# Ethernet_Switch.net
KiCad netlist of a schematic drawn in Altium Designer
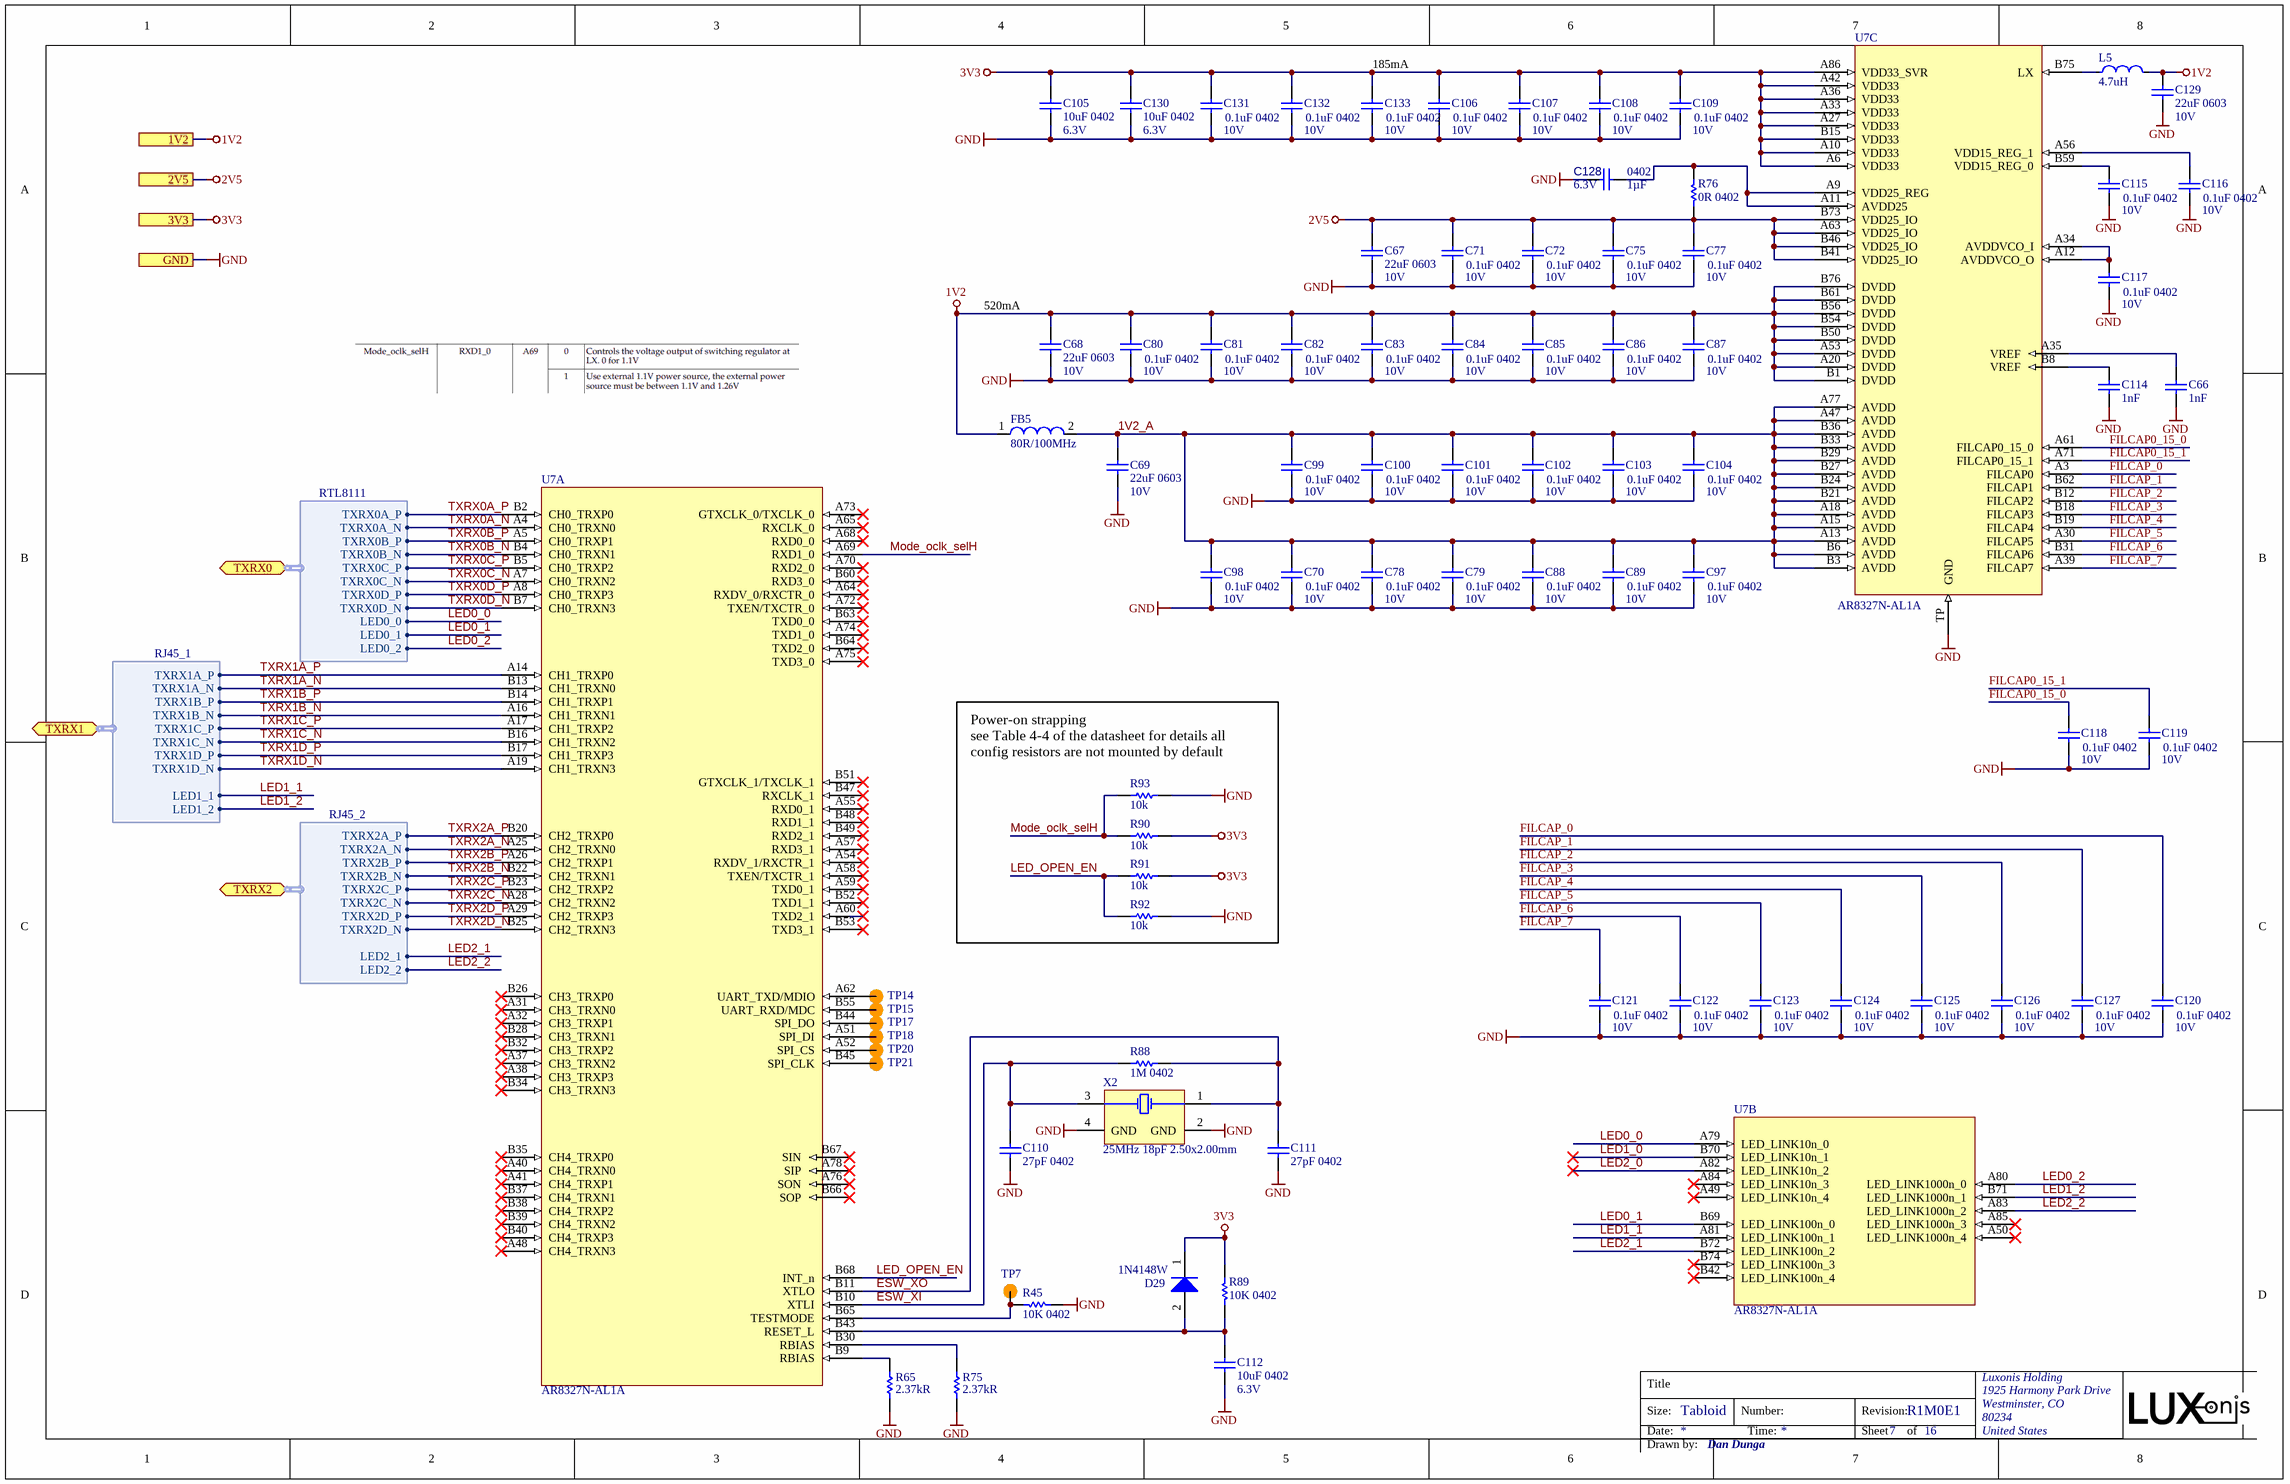
[diagram p0: Ethernet_Switch.SchDoc]

(export (version "E")
  (design (tool "Eeschema 10.0.6"))
  (components
    (comp (ref "C66")
      (value "1nF")
      (footprint "FP-GRM155-0_05-IPC_B")
      (description "0402 1000 pF 50 V ±5% Tolerance C0G Multilayer Ceramic Chip Capacitor")
      (fields (field (name "TOLERANCE") "5%") (field (name "Comment") "GRM1555C1H102JA01D"))
      (libsource (lib "Luxonis LLC") (part "CAP-NP-2"))
    )
    (comp (ref "C67")
      (value "22uF 0603")
      (footprint "CAPC0603(1608)100_N")
      (description "CAP CER 22UF 10V X5R 0603 20%")
      (fields (field (name "TOLERANCE") "20%") (field (name "VOLTAGE RATING") "10V"))
      (libsource (lib "LuxonisMaster") (part "GRM188R61A226ME15D"))
    )
    (comp (ref "C68")
      (value "22uF 0603")
      (footprint "CAPC0603(1608)100_N")
      (description "CAP CER 22UF 10V X5R 0603 20%")
      (fields (field (name "TOLERANCE") "20%") (field (name "VOLTAGE RATING") "10V"))
      (libsource (lib "LuxonisMaster") (part "GRM188R61A226ME15D"))
    )
    (comp (ref "C69")
      (value "22uF 0603")
      (footprint "CAPC0603(1608)100_N")
      (description "CAP CER 22UF 10V X5R 0603 20%")
      (fields (field (name "TOLERANCE") "20%") (field (name "VOLTAGE RATING") "10V"))
      (libsource (lib "LuxonisMaster") (part "GRM188R61A226ME15D"))
    )
    (comp (ref "C70")
      (value "0.1uF 0402")
      (footprint "CAPC0402(1005)70_N")
      (description "CAP CER 0.1UF 10V X7R 0402 5%")
      (fields (field (name "TOLERANCE") "5%") (field (name "VOLTAGE RATING") "10V"))
      (libsource (lib "LuxonisMaster") (part "GRM155R71A104JA01D"))
    )
    (comp (ref "C71")
      (value "0.1uF 0402")
      (footprint "CAPC0402(1005)70_N")
      (description "CAP CER 0.1UF 10V X7R 0402 5%")
      (fields (field (name "TOLERANCE") "5%") (field (name "VOLTAGE RATING") "10V"))
      (libsource (lib "LuxonisMaster") (part "GRM155R71A104JA01D"))
    )
    (comp (ref "C72")
      (value "0.1uF 0402")
      (footprint "CAPC0402(1005)70_N")
      (description "CAP CER 0.1UF 10V X7R 0402 5%")
      (fields (field (name "TOLERANCE") "5%") (field (name "VOLTAGE RATING") "10V"))
      (libsource (lib "LuxonisMaster") (part "GRM155R71A104JA01D"))
    )
    (comp (ref "C75")
      (value "0.1uF 0402")
      (footprint "CAPC0402(1005)70_N")
      (description "CAP CER 0.1UF 10V X7R 0402 5%")
      (fields (field (name "TOLERANCE") "5%") (field (name "VOLTAGE RATING") "10V"))
      (libsource (lib "LuxonisMaster") (part "GRM155R71A104JA01D"))
    )
    (comp (ref "C77")
      (value "0.1uF 0402")
      (footprint "CAPC0402(1005)70_N")
      (description "CAP CER 0.1UF 10V X7R 0402 5%")
      (fields (field (name "TOLERANCE") "5%") (field (name "VOLTAGE RATING") "10V"))
      (libsource (lib "LuxonisMaster") (part "GRM155R71A104JA01D"))
    )
    (comp (ref "C78")
      (value "0.1uF 0402")
      (footprint "CAPC0402(1005)70_N")
      (description "CAP CER 0.1UF 10V X7R 0402 5%")
      (fields (field (name "TOLERANCE") "5%") (field (name "VOLTAGE RATING") "10V"))
      (libsource (lib "LuxonisMaster") (part "GRM155R71A104JA01D"))
    )
    (comp (ref "C79")
      (value "0.1uF 0402")
      (footprint "CAPC0402(1005)70_N")
      (description "CAP CER 0.1UF 10V X7R 0402 5%")
      (fields (field (name "TOLERANCE") "5%") (field (name "VOLTAGE RATING") "10V"))
      (libsource (lib "LuxonisMaster") (part "GRM155R71A104JA01D"))
    )
    (comp (ref "C80")
      (value "0.1uF 0402")
      (footprint "CAPC0402(1005)70_N")
      (description "CAP CER 0.1UF 10V X7R 0402 5%")
      (fields (field (name "TOLERANCE") "5%") (field (name "VOLTAGE RATING") "10V"))
      (libsource (lib "LuxonisMaster") (part "GRM155R71A104JA01D"))
    )
    (comp (ref "C81")
      (value "0.1uF 0402")
      (footprint "CAPC0402(1005)70_N")
      (description "CAP CER 0.1UF 10V X7R 0402 5%")
      (fields (field (name "TOLERANCE") "5%") (field (name "VOLTAGE RATING") "10V"))
      (libsource (lib "LuxonisMaster") (part "GRM155R71A104JA01D"))
    )
    (comp (ref "C82")
      (value "0.1uF 0402")
      (footprint "CAPC0402(1005)70_N")
      (description "CAP CER 0.1UF 10V X7R 0402 5%")
      (fields (field (name "TOLERANCE") "5%") (field (name "VOLTAGE RATING") "10V"))
      (libsource (lib "LuxonisMaster") (part "GRM155R71A104JA01D"))
    )
    (comp (ref "C83")
      (value "0.1uF 0402")
      (footprint "CAPC0402(1005)70_N")
      (description "CAP CER 0.1UF 10V X7R 0402 5%")
      (fields (field (name "TOLERANCE") "5%") (field (name "VOLTAGE RATING") "10V"))
      (libsource (lib "LuxonisMaster") (part "GRM155R71A104JA01D"))
    )
    (comp (ref "C84")
      (value "0.1uF 0402")
      (footprint "CAPC0402(1005)70_N")
      (description "CAP CER 0.1UF 10V X7R 0402 5%")
      (fields (field (name "TOLERANCE") "5%") (field (name "VOLTAGE RATING") "10V"))
      (libsource (lib "LuxonisMaster") (part "GRM155R71A104JA01D"))
    )
    (comp (ref "C85")
      (value "0.1uF 0402")
      (footprint "CAPC0402(1005)70_N")
      (description "CAP CER 0.1UF 10V X7R 0402 5%")
      (fields (field (name "TOLERANCE") "5%") (field (name "VOLTAGE RATING") "10V"))
      (libsource (lib "LuxonisMaster") (part "GRM155R71A104JA01D"))
    )
    (comp (ref "C86")
      (value "0.1uF 0402")
      (footprint "CAPC0402(1005)70_N")
      (description "CAP CER 0.1UF 10V X7R 0402 5%")
      (fields (field (name "TOLERANCE") "5%") (field (name "VOLTAGE RATING") "10V"))
      (libsource (lib "LuxonisMaster") (part "GRM155R71A104JA01D"))
    )
    (comp (ref "C87")
      (value "0.1uF 0402")
      (footprint "CAPC0402(1005)70_N")
      (description "CAP CER 0.1UF 10V X7R 0402 5%")
      (fields (field (name "TOLERANCE") "5%") (field (name "VOLTAGE RATING") "10V"))
      (libsource (lib "LuxonisMaster") (part "GRM155R71A104JA01D"))
    )
    (comp (ref "C88")
      (value "0.1uF 0402")
      (footprint "CAPC0402(1005)70_N")
      (description "CAP CER 0.1UF 10V X7R 0402 5%")
      (fields (field (name "TOLERANCE") "5%") (field (name "VOLTAGE RATING") "10V"))
      (libsource (lib "LuxonisMaster") (part "GRM155R71A104JA01D"))
    )
    (comp (ref "C89")
      (value "0.1uF 0402")
      (footprint "CAPC0402(1005)70_N")
      (description "CAP CER 0.1UF 10V X7R 0402 5%")
      (fields (field (name "TOLERANCE") "5%") (field (name "VOLTAGE RATING") "10V"))
      (libsource (lib "LuxonisMaster") (part "GRM155R71A104JA01D"))
    )
    (comp (ref "C97")
      (value "0.1uF 0402")
      (footprint "CAPC0402(1005)70_N")
      (description "CAP CER 0.1UF 10V X7R 0402 5%")
      (fields (field (name "TOLERANCE") "5%") (field (name "VOLTAGE RATING") "10V"))
      (libsource (lib "LuxonisMaster") (part "GRM155R71A104JA01D"))
    )
    (comp (ref "C98")
      (value "0.1uF 0402")
      (footprint "CAPC0402(1005)70_N")
      (description "CAP CER 0.1UF 10V X7R 0402 5%")
      (fields (field (name "TOLERANCE") "5%") (field (name "VOLTAGE RATING") "10V"))
      (libsource (lib "LuxonisMaster") (part "GRM155R71A104JA01D"))
    )
    (comp (ref "C99")
      (value "0.1uF 0402")
      (footprint "CAPC0402(1005)70_N")
      (description "CAP CER 0.1UF 10V X7R 0402 5%")
      (fields (field (name "TOLERANCE") "5%") (field (name "VOLTAGE RATING") "10V"))
      (libsource (lib "LuxonisMaster") (part "GRM155R71A104JA01D"))
    )
    (comp (ref "C100")
      (value "0.1uF 0402")
      (footprint "CAPC0402(1005)70_N")
      (description "CAP CER 0.1UF 10V X7R 0402 5%")
      (fields (field (name "TOLERANCE") "5%") (field (name "VOLTAGE RATING") "10V"))
      (libsource (lib "LuxonisMaster") (part "GRM155R71A104JA01D"))
    )
    (comp (ref "C101")
      (value "0.1uF 0402")
      (footprint "CAPC0402(1005)70_N")
      (description "CAP CER 0.1UF 10V X7R 0402 5%")
      (fields (field (name "TOLERANCE") "5%") (field (name "VOLTAGE RATING") "10V"))
      (libsource (lib "LuxonisMaster") (part "GRM155R71A104JA01D"))
    )
    (comp (ref "C102")
      (value "0.1uF 0402")
      (footprint "CAPC0402(1005)70_N")
      (description "CAP CER 0.1UF 10V X7R 0402 5%")
      (fields (field (name "TOLERANCE") "5%") (field (name "VOLTAGE RATING") "10V"))
      (libsource (lib "LuxonisMaster") (part "GRM155R71A104JA01D"))
    )
    (comp (ref "C103")
      (value "0.1uF 0402")
      (footprint "CAPC0402(1005)70_N")
      (description "CAP CER 0.1UF 10V X7R 0402 5%")
      (fields (field (name "TOLERANCE") "5%") (field (name "VOLTAGE RATING") "10V"))
      (libsource (lib "LuxonisMaster") (part "GRM155R71A104JA01D"))
    )
    (comp (ref "C104")
      (value "0.1uF 0402")
      (footprint "CAPC0402(1005)70_N")
      (description "CAP CER 0.1UF 10V X7R 0402 5%")
      (fields (field (name "TOLERANCE") "5%") (field (name "VOLTAGE RATING") "10V"))
      (libsource (lib "LuxonisMaster") (part "GRM155R71A104JA01D"))
    )
    (comp (ref "C105")
      (value "10uF 0402")
      (footprint "CAPC0402(1005)70_N")
      (description "CAP CER 10UF 6.3V X5R 0402 20%")
      (fields (field (name "TOLERANCE") "20%") (field (name "VOLTAGE RATING") "6.3V"))
      (libsource (lib "LuxonisMaster") (part "GRM155R60J106ME15D"))
    )
    (comp (ref "C106")
      (value "0.1uF 0402")
      (footprint "CAPC0402(1005)70_N")
      (description "CAP CER 0.1UF 10V X7R 0402 5%")
      (fields (field (name "TOLERANCE") "5%") (field (name "VOLTAGE RATING") "10V"))
      (libsource (lib "LuxonisMaster") (part "GRM155R71A104JA01D"))
    )
    (comp (ref "C107")
      (value "0.1uF 0402")
      (footprint "CAPC0402(1005)70_N")
      (description "CAP CER 0.1UF 10V X7R 0402 5%")
      (fields (field (name "TOLERANCE") "5%") (field (name "VOLTAGE RATING") "10V"))
      (libsource (lib "LuxonisMaster") (part "GRM155R71A104JA01D"))
    )
    (comp (ref "C108")
      (value "0.1uF 0402")
      (footprint "CAPC0402(1005)70_N")
      (description "CAP CER 0.1UF 10V X7R 0402 5%")
      (fields (field (name "TOLERANCE") "5%") (field (name "VOLTAGE RATING") "10V"))
      (libsource (lib "LuxonisMaster") (part "GRM155R71A104JA01D"))
    )
    (comp (ref "C109")
      (value "0.1uF 0402")
      (footprint "CAPC0402(1005)70_N")
      (description "CAP CER 0.1UF 10V X7R 0402 5%")
      (fields (field (name "TOLERANCE") "5%") (field (name "VOLTAGE RATING") "10V"))
      (libsource (lib "LuxonisMaster") (part "GRM155R71A104JA01D"))
    )
    (comp (ref "C110")
      (value "27pF 0402")
      (footprint "CAPC0402(1005)60_N")
      (description "CAP CER 27PF 50V C0G/NP0 0402")
      (fields (field (name "TOLERANCE") "5%") (field (name "VOLTAGE") "50V"))
      (libsource (lib "BW2098POE") (part "C0402C270J5GACTU"))
    )
    (comp (ref "C111")
      (value "27pF 0402")
      (footprint "CAPC0402(1005)60_N")
      (description "CAP CER 27PF 50V C0G/NP0 0402")
      (fields (field (name "TOLERANCE") "5%") (field (name "VOLTAGE") "50V"))
      (libsource (lib "BW2098POE") (part "C0402C270J5GACTU"))
    )
    (comp (ref "C112")
      (value "10uF 0402")
      (footprint "CAPC0402(1005)70_N")
      (description "CAP CER 10UF 6.3V X5R 0402 20%")
      (fields (field (name "TOLERANCE") "20%") (field (name "VOLTAGE RATING") "6.3V"))
      (libsource (lib "LuxonisMaster") (part "GRM155R60J106ME15D"))
    )
    (comp (ref "C114")
      (value "1nF")
      (footprint "FP-GRM155-0_05-IPC_B")
      (description "0402 1000 pF 50 V ±5% Tolerance C0G Multilayer Ceramic Chip Capacitor")
      (fields (field (name "TOLERANCE") "5%") (field (name "Comment") "GRM1555C1H102JA01D"))
      (libsource (lib "Luxonis LLC") (part "CAP-NP-2"))
    )
    (comp (ref "C115")
      (value "0.1uF 0402")
      (footprint "CAPC0402(1005)70_N")
      (description "CAP CER 0.1UF 10V X7R 0402 5%")
      (fields (field (name "TOLERANCE") "5%") (field (name "VOLTAGE RATING") "10V"))
      (libsource (lib "LuxonisMaster") (part "GRM155R71A104JA01D"))
    )
    (comp (ref "C116")
      (value "0.1uF 0402")
      (footprint "CAPC0402(1005)70_N")
      (description "CAP CER 0.1UF 10V X7R 0402 5%")
      (fields (field (name "TOLERANCE") "5%") (field (name "VOLTAGE RATING") "10V"))
      (libsource (lib "LuxonisMaster") (part "GRM155R71A104JA01D"))
    )
    (comp (ref "C117")
      (value "0.1uF 0402")
      (footprint "CAPC0402(1005)70_N")
      (description "CAP CER 0.1UF 10V X7R 0402 5%")
      (fields (field (name "TOLERANCE") "5%") (field (name "VOLTAGE RATING") "10V"))
      (libsource (lib "LuxonisMaster") (part "GRM155R71A104JA01D"))
    )
    (comp (ref "C118")
      (value "0.1uF 0402")
      (footprint "CAPC0402(1005)70_N")
      (description "CAP CER 0.1UF 10V X7R 0402 5%")
      (fields (field (name "TOLERANCE") "5%") (field (name "VOLTAGE RATING") "10V"))
      (libsource (lib "LuxonisMaster") (part "GRM155R71A104JA01D"))
    )
    (comp (ref "C119")
      (value "0.1uF 0402")
      (footprint "CAPC0402(1005)70_N")
      (description "CAP CER 0.1UF 10V X7R 0402 5%")
      (fields (field (name "TOLERANCE") "5%") (field (name "VOLTAGE RATING") "10V"))
      (libsource (lib "LuxonisMaster") (part "GRM155R71A104JA01D"))
    )
    (comp (ref "C120")
      (value "0.1uF 0402")
      (footprint "CAPC0402(1005)70_N")
      (description "CAP CER 0.1UF 10V X7R 0402 5%")
      (fields (field (name "TOLERANCE") "5%") (field (name "VOLTAGE RATING") "10V"))
      (libsource (lib "LuxonisMaster") (part "GRM155R71A104JA01D"))
    )
    (comp (ref "C121")
      (value "0.1uF 0402")
      (footprint "CAPC0402(1005)70_N")
      (description "CAP CER 0.1UF 10V X7R 0402 5%")
      (fields (field (name "TOLERANCE") "5%") (field (name "VOLTAGE RATING") "10V"))
      (libsource (lib "LuxonisMaster") (part "GRM155R71A104JA01D"))
    )
    (comp (ref "C122")
      (value "0.1uF 0402")
      (footprint "CAPC0402(1005)70_N")
      (description "CAP CER 0.1UF 10V X7R 0402 5%")
      (fields (field (name "TOLERANCE") "5%") (field (name "VOLTAGE RATING") "10V"))
      (libsource (lib "LuxonisMaster") (part "GRM155R71A104JA01D"))
    )
    (comp (ref "C123")
      (value "0.1uF 0402")
      (footprint "CAPC0402(1005)70_N")
      (description "CAP CER 0.1UF 10V X7R 0402 5%")
      (fields (field (name "TOLERANCE") "5%") (field (name "VOLTAGE RATING") "10V"))
      (libsource (lib "LuxonisMaster") (part "GRM155R71A104JA01D"))
    )
    (comp (ref "C124")
      (value "0.1uF 0402")
      (footprint "CAPC0402(1005)70_N")
      (description "CAP CER 0.1UF 10V X7R 0402 5%")
      (fields (field (name "TOLERANCE") "5%") (field (name "VOLTAGE RATING") "10V"))
      (libsource (lib "LuxonisMaster") (part "GRM155R71A104JA01D"))
    )
    (comp (ref "C125")
      (value "0.1uF 0402")
      (footprint "CAPC0402(1005)70_N")
      (description "CAP CER 0.1UF 10V X7R 0402 5%")
      (fields (field (name "TOLERANCE") "5%") (field (name "VOLTAGE RATING") "10V"))
      (libsource (lib "LuxonisMaster") (part "GRM155R71A104JA01D"))
    )
    (comp (ref "C126")
      (value "0.1uF 0402")
      (footprint "CAPC0402(1005)70_N")
      (description "CAP CER 0.1UF 10V X7R 0402 5%")
      (fields (field (name "TOLERANCE") "5%") (field (name "VOLTAGE RATING") "10V"))
      (libsource (lib "LuxonisMaster") (part "GRM155R71A104JA01D"))
    )
    (comp (ref "C127")
      (value "0.1uF 0402")
      (footprint "CAPC0402(1005)70_N")
      (description "CAP CER 0.1UF 10V X7R 0402 5%")
      (fields (field (name "TOLERANCE") "5%") (field (name "VOLTAGE RATING") "10V"))
      (libsource (lib "LuxonisMaster") (part "GRM155R71A104JA01D"))
    )
    (comp (ref "C128")
      (value "1µF")
      (footprint "CAPC1005X55X25LL05T10")
      (description "CAP CER 1UF 6.3V X5R 0402 10%")
      (fields
        (field (name "CASE/PACKAGE") "0402")
        (field (name "TOLERANCE") "10%")
        (field (name "VOLTAGE RATING") "6.3V")
        (field (name "Comment") "04026D105KAT2A")
      )
      (libsource (lib "Luxonis LLC") (part "*"))
    )
    (comp (ref "C129")
      (value "22uF 0603")
      (footprint "CAPC0603(1608)100_N")
      (description "CAP CER 22UF 10V X5R 0603 20%")
      (fields (field (name "TOLERANCE") "20%") (field (name "VOLTAGE RATING") "10V"))
      (libsource (lib "LuxonisMaster") (part "GRM188R61A226ME15D"))
    )
    (comp (ref "C130")
      (value "10uF 0402")
      (footprint "CAPC0402(1005)70_N")
      (description "CAP CER 10UF 6.3V X5R 0402 20%")
      (fields (field (name "TOLERANCE") "20%") (field (name "VOLTAGE RATING") "6.3V"))
      (libsource (lib "LuxonisMaster") (part "GRM155R60J106ME15D"))
    )
    (comp (ref "C131")
      (value "0.1uF 0402")
      (footprint "CAPC0402(1005)70_N")
      (description "CAP CER 0.1UF 10V X7R 0402 5%")
      (fields (field (name "TOLERANCE") "5%") (field (name "VOLTAGE RATING") "10V"))
      (libsource (lib "LuxonisMaster") (part "GRM155R71A104JA01D"))
    )
    (comp (ref "C132")
      (value "0.1uF 0402")
      (footprint "CAPC0402(1005)70_N")
      (description "CAP CER 0.1UF 10V X7R 0402 5%")
      (fields (field (name "TOLERANCE") "5%") (field (name "VOLTAGE RATING") "10V"))
      (libsource (lib "LuxonisMaster") (part "GRM155R71A104JA01D"))
    )
    (comp (ref "C133")
      (value "0.1uF 0402")
      (footprint "CAPC0402(1005)70_N")
      (description "CAP CER 0.1UF 10V X7R 0402 5%")
      (fields (field (name "TOLERANCE") "5%") (field (name "VOLTAGE RATING") "10V"))
      (libsource (lib "LuxonisMaster") (part "GRM155R71A104JA01D"))
    )
    (comp (ref "D29")
      (value "1N4148W")
      (footprint "1N4148W-7-F")
      (description "DIODE GEN PURP 100V 300MA SOD123")
      (fields (field (name "VOLTAGE") "100V"))
      (libsource (lib "PCBProject") (part "1N4148W-7-F"))
    )
    (comp (ref "FB5")
      (value "80R/100MHz")
      (footprint "BK1608HS800-T_N")
      (description "FERRITE BEAD 80 OHM 0603 1LN")
      (fields (field (name "TOLERANCE") "25%"))
      (libsource (lib "LuxonisMaster") (part "BK1608HS800-T"))
    )
    (comp (ref "L5")
      (value "DFE252012P-4R7M=P2")
      (footprint "FP-DFE252012C-IPC_C")
      (description "Inductor Power Shielded Wirewound 4.7uH 20% 1MHz Metal 1.4A 0.2Ohm DCR 1008 T/R")
      (fields (field (name "INDUCTANCE") "4.7uH"))
      (libsource (lib "Luxonis LLC") (part "725321dda6339637d4d059423bc1c3c"))
    )
    (comp (ref "R45")
      (value "10K 0402")
      (footprint "RESC0402(1005)_N")
      (fields (field (name "TOLERANCE") "1%"))
      (libsource (lib "LuxonisMaster") (part "RC0402FR-1310KL"))
    )
    (comp (ref "R65")
      (value "ERJ-2RKF2371X")
      (footprint "RESC1005X40X25NL05T05")
      (description "Res Thick Film 0402 2.37K Ohm 1% 1/10W ±100ppm/°C Molded SMD Punched Carrier T/R")
      (fields (field (name "TOLERANCE") "1%") (field (name "RESISTANCE") "2.37kR"))
      (libsource (lib "Luxonis LLC") (part "RES"))
    )
    (comp (ref "R75")
      (value "ERJ-2RKF2371X")
      (footprint "RESC1005X40X25NL05T05")
      (description "Res Thick Film 0402 2.37K Ohm 1% 1/10W ±100ppm/°C Molded SMD Punched Carrier T/R")
      (fields (field (name "TOLERANCE") "1%") (field (name "RESISTANCE") "2.37kR"))
      (libsource (lib "Luxonis LLC") (part "RES"))
    )
    (comp (ref "R76")
      (value "0R 0402")
      (footprint "RESC0402(1005)_N")
      (fields (field (name "TOLERANCE") "1%"))
      (libsource (lib "LuxonisMaster") (part "RC0402FR-1310KL"))
    )
    (comp (ref "R88")
      (value "1M 0402")
      (footprint "RESC0402(1005)_N")
      (description "RES SMD 1M OHM 1% 1/16W 0402")
      (fields (field (name "TOLERANCE") "1%"))
      (libsource (lib "LuxonisMaster") (part "RC0402FR-071ML"))
    )
    (comp (ref "R89")
      (value "10K 0402")
      (footprint "RESC0402(1005)_N")
      (fields (field (name "TOLERANCE") "1%"))
      (libsource (lib "LuxonisMaster") (part "RC0402FR-1310KL"))
    )
    (comp (ref "R90")
      (value "10k")
      (footprint "RESC0402(1005)_N")
      (fields (field (name "TOLERANCE") "1%") (field (name "Comment") "RC0402FR-1310KL"))
      (libsource (lib "Luxonis LLC") (part "CR0402-FX-2492GLF"))
    )
    (comp (ref "R91")
      (value "10k")
      (footprint "RESC0402(1005)_N")
      (fields (field (name "TOLERANCE") "1%") (field (name "Comment") "RC0402FR-1310KL"))
      (libsource (lib "Luxonis LLC") (part "CR0402-FX-2492GLF"))
    )
    (comp (ref "R92")
      (value "10k")
      (footprint "RESC0402(1005)_N")
      (fields (field (name "TOLERANCE") "1%") (field (name "Comment") "RC0402FR-1310KL"))
      (libsource (lib "Luxonis LLC") (part "CR0402-FX-2492GLF"))
    )
    (comp (ref "R93")
      (value "10k")
      (footprint "RESC0402(1005)_N")
      (fields (field (name "TOLERANCE") "1%") (field (name "Comment") "RC0402FR-1310KL"))
      (libsource (lib "Luxonis LLC") (part "CR0402-FX-2492GLF"))
    )
    (comp (ref "TP7")
      (value "TP075_150_NS")
      (footprint "LuxonisMaster:TP075_150_NS")
      (libsource (lib "LuxonisMaster") (part "TEST_POINT"))
    )
    (comp (ref "TP14")
      (value "TP075_150_NS")
      (footprint "LuxonisMaster:TP075_150_NS")
      (libsource (lib "LuxonisMaster") (part "TEST_POINT"))
    )
    (comp (ref "TP15")
      (value "TP075_150_NS")
      (footprint "LuxonisMaster:TP075_150_NS")
      (libsource (lib "LuxonisMaster") (part "TEST_POINT"))
    )
    (comp (ref "TP17")
      (value "TP075_150_NS")
      (footprint "LuxonisMaster:TP075_150_NS")
      (libsource (lib "LuxonisMaster") (part "TEST_POINT"))
    )
    (comp (ref "TP18")
      (value "TP075_150_NS")
      (footprint "LuxonisMaster:TP075_150_NS")
      (libsource (lib "LuxonisMaster") (part "TEST_POINT"))
    )
    (comp (ref "TP20")
      (value "TP075_150_NS")
      (footprint "LuxonisMaster:TP075_150_NS")
      (libsource (lib "LuxonisMaster") (part "TEST_POINT"))
    )
    (comp (ref "TP21")
      (value "TP075_150_NS")
      (footprint "LuxonisMaster:TP075_150_NS")
      (libsource (lib "LuxonisMaster") (part "TEST_POINT"))
    )
    (comp (ref "U7")
      (value "AR8327N-AL1A")
      (footprint "AR8327N-AL1A")
      (description "Seven-port Gigabit Ethernet Switch")
      (libsource (lib "AR8327N-AL1A") (part "AR8327N-AL1A"))
    )
    (comp (ref "X2")
      (value "25MHz 18pF 2.50x2.00mm")
      (footprint "ECS-250-18-36B-CKY-TR")
      (description "CRYSTAL 25.0000MHZ 18PF SMD 25MHz ±10ppm Crystal 18pF 50 Ohms 4-SMD, No Lead")
      (libsource (lib "BW2098POE") (part "ECS-250-18-36B-CKY-TR"))
    )
  )
  (nets
    (net (code "4") (name "/1V2_A") (class "Default")
      (node (ref "C100") (pin "2") (pinfunction "2_2") (pintype "passive"))
      (node (ref "C101") (pin "2") (pinfunction "2_2") (pintype "passive"))
      (node (ref "C102") (pin "2") (pinfunction "2_2") (pintype "passive"))
      (node (ref "C103") (pin "2") (pinfunction "2_2") (pintype "passive"))
      (node (ref "C104") (pin "2") (pinfunction "2_2") (pintype "passive"))
      (node (ref "C69") (pin "2") (pinfunction "2_2") (pintype "passive"))
      (node (ref "C70") (pin "2") (pinfunction "2_2") (pintype "passive"))
      (node (ref "C78") (pin "2") (pinfunction "2_2") (pintype "passive"))
      (node (ref "C79") (pin "2") (pinfunction "2_2") (pintype "passive"))
      (node (ref "C88") (pin "2") (pinfunction "2_2") (pintype "passive"))
      (node (ref "C89") (pin "2") (pinfunction "2_2") (pintype "passive"))
      (node (ref "C97") (pin "2") (pinfunction "2_2") (pintype "passive"))
      (node (ref "C98") (pin "2") (pinfunction "2_2") (pintype "passive"))
      (node (ref "C99") (pin "2") (pinfunction "2_2") (pintype "passive"))
      (node (ref "FB5") (pin "2") (pinfunction "2_2") (pintype "passive"))
      (node (ref "U7") (pin "A13") (pinfunction "AVDD_A13") (pintype "input"))
      (node (ref "U7") (pin "A15") (pinfunction "AVDD_A15") (pintype "input"))
      (node (ref "U7") (pin "A18") (pinfunction "AVDD_A18") (pintype "input"))
      (node (ref "U7") (pin "A47") (pinfunction "AVDD_A47") (pintype "input"))
      (node (ref "U7") (pin "A77") (pinfunction "AVDD_A77") (pintype "input"))
      (node (ref "U7") (pin "B21") (pinfunction "AVDD_B21") (pintype "input"))
      (node (ref "U7") (pin "B24") (pinfunction "AVDD_B24") (pintype "input"))
      (node (ref "U7") (pin "B27") (pinfunction "AVDD_B27") (pintype "input"))
      (node (ref "U7") (pin "B29") (pinfunction "AVDD_B29") (pintype "input"))
      (node (ref "U7") (pin "B3") (pinfunction "AVDD_B3") (pintype "input"))
      (node (ref "U7") (pin "B33") (pinfunction "AVDD_B33") (pintype "input"))
      (node (ref "U7") (pin "B36") (pinfunction "AVDD_B36") (pintype "input"))
      (node (ref "U7") (pin "B6") (pinfunction "AVDD_B6") (pintype "input"))
    )
    (net (code "5") (name "/ESW_XI") (class "Default")
      (node (ref "C110") (pin "2") (pinfunction "2_2") (pintype "passive"))
      (node (ref "R88") (pin "1") (pinfunction "1_1") (pintype "passive"))
      (node (ref "U7") (pin "B10") (pinfunction "XTLI_B10") (pintype "input"))
      (node (ref "X2") (pin "3") (pinfunction "X2_3") (pintype "passive"))
    )
    (net (code "6") (name "/ESW_XO") (class "Default")
      (node (ref "C111") (pin "2") (pinfunction "2_2") (pintype "passive"))
      (node (ref "R88") (pin "2") (pinfunction "2_2") (pintype "passive"))
      (node (ref "U7") (pin "B11") (pinfunction "XTLO_B11") (pintype "input"))
      (node (ref "X2") (pin "1") (pinfunction "X1_1") (pintype "passive"))
    )
    (net (code "7") (name "/FILCAP0_15_0") (class "Default")
      (node (ref "C118") (pin "2") (pinfunction "2_2") (pintype "passive"))
      (node (ref "U7") (pin "A61") (pinfunction "FILCAP0_15_0_A61") (pintype "input"))
    )
    (net (code "8") (name "/FILCAP0_15_1") (class "Default")
      (node (ref "C119") (pin "2") (pinfunction "2_2") (pintype "passive"))
      (node (ref "U7") (pin "A71") (pinfunction "FILCAP0_15_1_A71") (pintype "input"))
    )
    (net (code "9") (name "/FILCAP_0") (class "Default")
      (node (ref "C120") (pin "2") (pinfunction "2_2") (pintype "passive"))
      (node (ref "U7") (pin "A3") (pinfunction "FILCAP0_A3") (pintype "input"))
    )
    (net (code "10") (name "/FILCAP_1") (class "Default")
      (node (ref "C127") (pin "2") (pinfunction "2_2") (pintype "passive"))
      (node (ref "U7") (pin "B62") (pinfunction "FILCAP1_B62") (pintype "input"))
    )
    (net (code "11") (name "/FILCAP_2") (class "Default")
      (node (ref "C126") (pin "2") (pinfunction "2_2") (pintype "passive"))
      (node (ref "U7") (pin "B12") (pinfunction "FILCAP2_B12") (pintype "input"))
    )
    (net (code "12") (name "/FILCAP_3") (class "Default")
      (node (ref "C125") (pin "2") (pinfunction "2_2") (pintype "passive"))
      (node (ref "U7") (pin "B18") (pinfunction "FILCAP3_B18") (pintype "input"))
    )
    (net (code "13") (name "/FILCAP_4") (class "Default")
      (node (ref "C124") (pin "2") (pinfunction "2_2") (pintype "passive"))
      (node (ref "U7") (pin "B19") (pinfunction "FILCAP4_B19") (pintype "input"))
    )
    (net (code "14") (name "/FILCAP_5") (class "Default")
      (node (ref "C123") (pin "2") (pinfunction "2_2") (pintype "passive"))
      (node (ref "U7") (pin "A30") (pinfunction "FILCAP5_A30") (pintype "input"))
    )
    (net (code "15") (name "/FILCAP_6") (class "Default")
      (node (ref "C122") (pin "2") (pinfunction "2_2") (pintype "passive"))
      (node (ref "U7") (pin "B31") (pinfunction "FILCAP6_B31") (pintype "input"))
    )
    (net (code "16") (name "/FILCAP_7") (class "Default")
      (node (ref "C121") (pin "2") (pinfunction "2_2") (pintype "passive"))
      (node (ref "U7") (pin "A39") (pinfunction "FILCAP7_A39") (pintype "input"))
    )
    (net (code "17") (name "/LED0_0") (class "Default")
      (node (ref "U7") (pin "A79") (pinfunction "LED_LINK10n_0_A79") (pintype "input"))
    )
    (net (code "18") (name "/LED0_1") (class "Default")
      (node (ref "U7") (pin "B69") (pinfunction "LED_LINK100n_0_B69") (pintype "input"))
    )
    (net (code "19") (name "/LED0_2") (class "Default")
      (node (ref "U7") (pin "A80") (pinfunction "LED_LINK1000n_0_A80") (pintype "input"))
    )
    (net (code "20") (name "/LED1_0") (class "Default")
      (node (ref "U7") (pin "B70") (pinfunction "LED_LINK10n_1_B70") (pintype "input+no_connect"))
    )
    (net (code "21") (name "/LED1_1") (class "Default")
      (node (ref "U7") (pin "A81") (pinfunction "LED_LINK100n_1_A81") (pintype "input"))
    )
    (net (code "22") (name "/LED1_2") (class "Default")
      (node (ref "U7") (pin "B71") (pinfunction "LED_LINK1000n_1_B71") (pintype "input"))
    )
    (net (code "23") (name "/LED2_0") (class "Default")
      (node (ref "U7") (pin "A82") (pinfunction "LED_LINK10n_2_A82") (pintype "input+no_connect"))
    )
    (net (code "24") (name "/LED2_1") (class "Default")
      (node (ref "U7") (pin "B72") (pinfunction "LED_LINK100n_2_B72") (pintype "input"))
    )
    (net (code "25") (name "/LED2_2") (class "Default")
      (node (ref "U7") (pin "A83") (pinfunction "LED_LINK1000n_2_A83") (pintype "input"))
    )
    (net (code "26") (name "/LED_OPEN_EN") (class "Default")
      (node (ref "R91") (pin "1") (pinfunction "1_1") (pintype "passive"))
      (node (ref "R92") (pin "1") (pinfunction "1_1") (pintype "passive"))
      (node (ref "U7") (pin "B68") (pinfunction "INT_n_B68") (pintype "input"))
    )
    (net (code "27") (name "/Mode_oclk_selH") (class "Default")
      (node (ref "R90") (pin "1") (pinfunction "1_1") (pintype "passive"))
      (node (ref "R93") (pin "1") (pinfunction "1_1") (pintype "passive"))
      (node (ref "U7") (pin "A69") (pinfunction "RXD1_0_A69") (pintype "input"))
    )
    (net (code "28") (name "/TXRX0A_N") (class "Default")
      (node (ref "U7") (pin "A4") (pinfunction "CH0_TRXN0_A4") (pintype "input"))
    )
    (net (code "29") (name "/TXRX0A_P") (class "Default")
      (node (ref "U7") (pin "B2") (pinfunction "CH0_TRXP0_B2") (pintype "input"))
    )
    (net (code "30") (name "/TXRX0B_N") (class "Default")
      (node (ref "U7") (pin "B4") (pinfunction "CH0_TRXN1_B4") (pintype "input"))
    )
    (net (code "31") (name "/TXRX0B_P") (class "Default")
      (node (ref "U7") (pin "A5") (pinfunction "CH0_TRXP1_A5") (pintype "input"))
    )
    (net (code "32") (name "/TXRX0C_N") (class "Default")
      (node (ref "U7") (pin "A7") (pinfunction "CH0_TRXN2_A7") (pintype "input"))
    )
    (net (code "33") (name "/TXRX0C_P") (class "Default")
      (node (ref "U7") (pin "B5") (pinfunction "CH0_TRXP2_B5") (pintype "input"))
    )
    (net (code "34") (name "/TXRX0D_N") (class "Default")
      (node (ref "U7") (pin "B7") (pinfunction "CH0_TRXN3_B7") (pintype "input"))
    )
    (net (code "35") (name "/TXRX0D_P") (class "Default")
      (node (ref "U7") (pin "A8") (pinfunction "CH0_TRXP3_A8") (pintype "input"))
    )
    (net (code "36") (name "/TXRX1A_N") (class "Default")
      (node (ref "U7") (pin "B13") (pinfunction "CH1_TRXN0_B13") (pintype "input"))
    )
    (net (code "37") (name "/TXRX1A_P") (class "Default")
      (node (ref "U7") (pin "A14") (pinfunction "CH1_TRXP0_A14") (pintype "input"))
    )
    (net (code "38") (name "/TXRX1B_N") (class "Default")
      (node (ref "U7") (pin "A16") (pinfunction "CH1_TRXN1_A16") (pintype "input"))
    )
    (net (code "39") (name "/TXRX1B_P") (class "Default")
      (node (ref "U7") (pin "B14") (pinfunction "CH1_TRXP1_B14") (pintype "input"))
    )
    (net (code "40") (name "/TXRX1C_N") (class "Default")
      (node (ref "U7") (pin "B16") (pinfunction "CH1_TRXN2_B16") (pintype "input"))
    )
    (net (code "41") (name "/TXRX1C_P") (class "Default")
      (node (ref "U7") (pin "A17") (pinfunction "CH1_TRXP2_A17") (pintype "input"))
    )
    (net (code "42") (name "/TXRX1D_N") (class "Default")
      (node (ref "U7") (pin "A19") (pinfunction "CH1_TRXN3_A19") (pintype "input"))
    )
    (net (code "43") (name "/TXRX1D_P") (class "Default")
      (node (ref "U7") (pin "B17") (pinfunction "CH1_TRXP3_B17") (pintype "input"))
    )
    (net (code "44") (name "/TXRX2A_N") (class "Default")
      (node (ref "U7") (pin "A25") (pinfunction "CH2_TRXN0_A25") (pintype "input"))
    )
    (net (code "45") (name "/TXRX2A_P") (class "Default")
      (node (ref "U7") (pin "B20") (pinfunction "CH2_TRXP0_B20") (pintype "input"))
    )
    (net (code "46") (name "/TXRX2B_N") (class "Default")
      (node (ref "U7") (pin "B22") (pinfunction "CH2_TRXN1_B22") (pintype "input"))
    )
    (net (code "47") (name "/TXRX2B_P") (class "Default")
      (node (ref "U7") (pin "A26") (pinfunction "CH2_TRXP1_A26") (pintype "input"))
    )
    (net (code "48") (name "/TXRX2C_N") (class "Default")
      (node (ref "U7") (pin "A28") (pinfunction "CH2_TRXN2_A28") (pintype "input"))
    )
    (net (code "49") (name "/TXRX2C_P") (class "Default")
      (node (ref "U7") (pin "B23") (pinfunction "CH2_TRXP2_B23") (pintype "input"))
    )
    (net (code "50") (name "/TXRX2D_N") (class "Default")
      (node (ref "U7") (pin "B25") (pinfunction "CH2_TRXN3_B25") (pintype "input"))
    )
    (net (code "51") (name "/TXRX2D_P") (class "Default")
      (node (ref "U7") (pin "A29") (pinfunction "CH2_TRXP3_A29") (pintype "input"))
    )
    (net (code "55") (name "1V2") (class "Default")
      (node (ref "C129") (pin "2") (pinfunction "2_2") (pintype "passive"))
      (node (ref "C68") (pin "2") (pinfunction "2_2") (pintype "passive"))
      (node (ref "C80") (pin "2") (pinfunction "2_2") (pintype "passive"))
      (node (ref "C81") (pin "2") (pinfunction "2_2") (pintype "passive"))
      (node (ref "C82") (pin "2") (pinfunction "2_2") (pintype "passive"))
      (node (ref "C83") (pin "2") (pinfunction "2_2") (pintype "passive"))
      (node (ref "C84") (pin "2") (pinfunction "2_2") (pintype "passive"))
      (node (ref "C85") (pin "2") (pinfunction "2_2") (pintype "passive"))
      (node (ref "C86") (pin "2") (pinfunction "2_2") (pintype "passive"))
      (node (ref "C87") (pin "2") (pinfunction "2_2") (pintype "passive"))
      (node (ref "FB5") (pin "1") (pinfunction "1_1") (pintype "passive"))
      (node (ref "L5") (pin "2") (pinfunction "2_2") (pintype "passive"))
      (node (ref "U7") (pin "A20") (pinfunction "DVDD_A20") (pintype "input"))
      (node (ref "U7") (pin "A53") (pinfunction "DVDD_A53") (pintype "input"))
      (node (ref "U7") (pin "B1") (pinfunction "DVDD_B1") (pintype "input"))
      (node (ref "U7") (pin "B50") (pinfunction "DVDD_B50") (pintype "input"))
      (node (ref "U7") (pin "B54") (pinfunction "DVDD_B54") (pintype "input"))
      (node (ref "U7") (pin "B56") (pinfunction "DVDD_B56") (pintype "input"))
      (node (ref "U7") (pin "B61") (pinfunction "DVDD_B61") (pintype "input"))
      (node (ref "U7") (pin "B76") (pinfunction "DVDD_B76") (pintype "input"))
    )
    (net (code "56") (name "2V5") (class "Default")
      (node (ref "C67") (pin "2") (pinfunction "2_2") (pintype "passive"))
      (node (ref "C71") (pin "2") (pinfunction "2_2") (pintype "passive"))
      (node (ref "C72") (pin "2") (pinfunction "2_2") (pintype "passive"))
      (node (ref "C75") (pin "2") (pinfunction "2_2") (pintype "passive"))
      (node (ref "C77") (pin "2") (pinfunction "2_2") (pintype "passive"))
      (node (ref "R76") (pin "1") (pinfunction "1_1") (pintype "passive"))
      (node (ref "U7") (pin "A63") (pinfunction "VDD25_IO_A63") (pintype "input"))
      (node (ref "U7") (pin "B41") (pinfunction "VDD25_IO_B41") (pintype "input"))
      (node (ref "U7") (pin "B46") (pinfunction "VDD25_IO_B46") (pintype "input"))
      (node (ref "U7") (pin "B73") (pinfunction "VDD25_IO_B73") (pintype "input"))
    )
    (net (code "57") (name "3V3") (class "Default")
      (node (ref "C105") (pin "2") (pinfunction "2_2") (pintype "passive"))
      (node (ref "C106") (pin "2") (pinfunction "2_2") (pintype "passive"))
      (node (ref "C107") (pin "2") (pinfunction "2_2") (pintype "passive"))
      (node (ref "C108") (pin "2") (pinfunction "2_2") (pintype "passive"))
      (node (ref "C109") (pin "2") (pinfunction "2_2") (pintype "passive"))
      (node (ref "C130") (pin "2") (pinfunction "2_2") (pintype "passive"))
      (node (ref "C131") (pin "2") (pinfunction "2_2") (pintype "passive"))
      (node (ref "C132") (pin "2") (pinfunction "2_2") (pintype "passive"))
      (node (ref "C133") (pin "2") (pinfunction "2_2") (pintype "passive"))
      (node (ref "D29") (pin "1") (pinfunction "K_1") (pintype "passive"))
      (node (ref "R89") (pin "1") (pinfunction "1_1") (pintype "passive"))
      (node (ref "R90") (pin "2") (pinfunction "2_2") (pintype "passive"))
      (node (ref "R91") (pin "2") (pinfunction "2_2") (pintype "passive"))
      (node (ref "U7") (pin "A10") (pinfunction "VDD33_A10") (pintype "input"))
      (node (ref "U7") (pin "A27") (pinfunction "VDD33_A27") (pintype "input"))
      (node (ref "U7") (pin "A33") (pinfunction "VDD33_A33") (pintype "input"))
      (node (ref "U7") (pin "A36") (pinfunction "VDD33_A36") (pintype "input"))
      (node (ref "U7") (pin "A42") (pinfunction "VDD33_A42") (pintype "input"))
      (node (ref "U7") (pin "A6") (pinfunction "VDD33_A6") (pintype "input"))
      (node (ref "U7") (pin "A86") (pinfunction "VDD33_SVR_A86") (pintype "input"))
      (node (ref "U7") (pin "B15") (pinfunction "VDD33_B15") (pintype "input"))
    )
    (net (code "58") (name "GND") (class "Default")
      (node (ref "C100") (pin "1") (pinfunction "1_1") (pintype "passive"))
      (node (ref "C101") (pin "1") (pinfunction "1_1") (pintype "passive"))
      (node (ref "C102") (pin "1") (pinfunction "1_1") (pintype "passive"))
      (node (ref "C103") (pin "1") (pinfunction "1_1") (pintype "passive"))
      (node (ref "C104") (pin "1") (pinfunction "1_1") (pintype "passive"))
      (node (ref "C105") (pin "1") (pinfunction "1_1") (pintype "passive"))
      (node (ref "C106") (pin "1") (pinfunction "1_1") (pintype "passive"))
      (node (ref "C107") (pin "1") (pinfunction "1_1") (pintype "passive"))
      (node (ref "C108") (pin "1") (pinfunction "1_1") (pintype "passive"))
      (node (ref "C109") (pin "1") (pinfunction "1_1") (pintype "passive"))
      (node (ref "C110") (pin "1") (pinfunction "1_1") (pintype "passive"))
      (node (ref "C111") (pin "1") (pinfunction "1_1") (pintype "passive"))
      (node (ref "C112") (pin "1") (pinfunction "1_1") (pintype "passive"))
      (node (ref "C114") (pin "1") (pinfunction "1_1") (pintype "passive"))
      (node (ref "C115") (pin "1") (pinfunction "1_1") (pintype "passive"))
      (node (ref "C116") (pin "1") (pinfunction "1_1") (pintype "passive"))
      (node (ref "C117") (pin "1") (pinfunction "1_1") (pintype "passive"))
      (node (ref "C118") (pin "1") (pinfunction "1_1") (pintype "passive"))
      (node (ref "C119") (pin "1") (pinfunction "1_1") (pintype "passive"))
      (node (ref "C120") (pin "1") (pinfunction "1_1") (pintype "passive"))
      (node (ref "C121") (pin "1") (pinfunction "1_1") (pintype "passive"))
      (node (ref "C122") (pin "1") (pinfunction "1_1") (pintype "passive"))
      (node (ref "C123") (pin "1") (pinfunction "1_1") (pintype "passive"))
      (node (ref "C124") (pin "1") (pinfunction "1_1") (pintype "passive"))
      (node (ref "C125") (pin "1") (pinfunction "1_1") (pintype "passive"))
      (node (ref "C126") (pin "1") (pinfunction "1_1") (pintype "passive"))
      (node (ref "C127") (pin "1") (pinfunction "1_1") (pintype "passive"))
      (node (ref "C128") (pin "2") (pinfunction "2_2") (pintype "passive"))
      (node (ref "C129") (pin "1") (pinfunction "1_1") (pintype "passive"))
      (node (ref "C130") (pin "1") (pinfunction "1_1") (pintype "passive"))
      (node (ref "C131") (pin "1") (pinfunction "1_1") (pintype "passive"))
      (node (ref "C132") (pin "1") (pinfunction "1_1") (pintype "passive"))
      (node (ref "C133") (pin "1") (pinfunction "1_1") (pintype "passive"))
      (node (ref "C66") (pin "1") (pinfunction "1_1") (pintype "passive"))
      (node (ref "C67") (pin "1") (pinfunction "1_1") (pintype "passive"))
      (node (ref "C68") (pin "1") (pinfunction "1_1") (pintype "passive"))
      (node (ref "C69") (pin "1") (pinfunction "1_1") (pintype "passive"))
      (node (ref "C70") (pin "1") (pinfunction "1_1") (pintype "passive"))
      (node (ref "C71") (pin "1") (pinfunction "1_1") (pintype "passive"))
      (node (ref "C72") (pin "1") (pinfunction "1_1") (pintype "passive"))
      (node (ref "C75") (pin "1") (pinfunction "1_1") (pintype "passive"))
      (node (ref "C77") (pin "1") (pinfunction "1_1") (pintype "passive"))
      (node (ref "C78") (pin "1") (pinfunction "1_1") (pintype "passive"))
      (node (ref "C79") (pin "1") (pinfunction "1_1") (pintype "passive"))
      (node (ref "C80") (pin "1") (pinfunction "1_1") (pintype "passive"))
      (node (ref "C81") (pin "1") (pinfunction "1_1") (pintype "passive"))
      (node (ref "C82") (pin "1") (pinfunction "1_1") (pintype "passive"))
      (node (ref "C83") (pin "1") (pinfunction "1_1") (pintype "passive"))
      (node (ref "C84") (pin "1") (pinfunction "1_1") (pintype "passive"))
      (node (ref "C85") (pin "1") (pinfunction "1_1") (pintype "passive"))
      (node (ref "C86") (pin "1") (pinfunction "1_1") (pintype "passive"))
      (node (ref "C87") (pin "1") (pinfunction "1_1") (pintype "passive"))
      (node (ref "C88") (pin "1") (pinfunction "1_1") (pintype "passive"))
      (node (ref "C89") (pin "1") (pinfunction "1_1") (pintype "passive"))
      (node (ref "C97") (pin "1") (pinfunction "1_1") (pintype "passive"))
      (node (ref "C98") (pin "1") (pinfunction "1_1") (pintype "passive"))
      (node (ref "C99") (pin "1") (pinfunction "1_1") (pintype "passive"))
      (node (ref "R45") (pin "1") (pinfunction "1_1") (pintype "passive"))
      (node (ref "R65") (pin "1") (pinfunction "1_1") (pintype "passive"))
      (node (ref "R75") (pin "1") (pinfunction "1_1") (pintype "passive"))
      (node (ref "R92") (pin "2") (pinfunction "2_2") (pintype "passive"))
      (node (ref "R93") (pin "2") (pinfunction "2_2") (pintype "passive"))
      (node (ref "U7") (pin "TP") (pinfunction "GND_TP") (pintype "input"))
      (node (ref "X2") (pin "2") (pinfunction "GND_2") (pintype "power_in"))
      (node (ref "X2") (pin "4") (pinfunction "GND_4") (pintype "power_in"))
    )
    (net (code "59") (name "Net-(C66-Pad2)") (class "Default")
      (node (ref "C66") (pin "2") (pinfunction "2_2") (pintype "passive"))
      (node (ref "U7") (pin "A35") (pinfunction "VREF_A35") (pintype "input"))
    )
    (net (code "60") (name "Net-(C114-Pad2)") (class "Default")
      (node (ref "C114") (pin "2") (pinfunction "2_2") (pintype "passive"))
      (node (ref "U7") (pin "B8") (pinfunction "VREF_B8") (pintype "input"))
    )
    (net (code "61") (name "Net-(D29-A)") (class "Default")
      (node (ref "C112") (pin "2") (pinfunction "2_2") (pintype "passive"))
      (node (ref "D29") (pin "2") (pinfunction "A_2") (pintype "passive"))
      (node (ref "R89") (pin "2") (pinfunction "2_2") (pintype "passive"))
      (node (ref "U7") (pin "B43") (pinfunction "RESET_L_B43") (pintype "input"))
    )
    (net (code "62") (name "Net-(R65-Pad2)") (class "Default")
      (node (ref "R65") (pin "2") (pinfunction "2_2") (pintype "passive"))
      (node (ref "U7") (pin "B9") (pinfunction "RBIAS_B9") (pintype "input"))
    )
    (net (code "63") (name "Net-(R75-Pad2)") (class "Default")
      (node (ref "R75") (pin "2") (pinfunction "2_2") (pintype "passive"))
      (node (ref "U7") (pin "B30") (pinfunction "RBIAS_B30") (pintype "input"))
    )
    (net (code "64") (name "Net-(U7A-SPI_CLK)") (class "Default")
      (node (ref "TP21") (pin "1") (pintype "passive"))
      (node (ref "U7") (pin "B45") (pinfunction "SPI_CLK_B45") (pintype "input"))
    )
    (net (code "65") (name "Net-(U7A-SPI_CS)") (class "Default")
      (node (ref "TP20") (pin "1") (pintype "passive"))
      (node (ref "U7") (pin "A52") (pinfunction "SPI_CS_A52") (pintype "input"))
    )
    (net (code "66") (name "Net-(U7A-SPI_DI)") (class "Default")
      (node (ref "TP18") (pin "1") (pintype "passive"))
      (node (ref "U7") (pin "A51") (pinfunction "SPI_DI_A51") (pintype "input"))
    )
    (net (code "67") (name "Net-(U7A-SPI_DO)") (class "Default")
      (node (ref "TP17") (pin "1") (pintype "passive"))
      (node (ref "U7") (pin "B44") (pinfunction "SPI_DO_B44") (pintype "input"))
    )
    (net (code "68") (name "Net-(U7A-TESTMODE)") (class "Default")
      (node (ref "R45") (pin "2") (pinfunction "2_2") (pintype "passive"))
      (node (ref "TP7") (pin "1") (pintype "passive"))
      (node (ref "U7") (pin "B65") (pinfunction "TESTMODE_B65") (pintype "input"))
    )
    (net (code "69") (name "Net-(U7A-UART_RXD{slash}MDC)") (class "Default")
      (node (ref "TP15") (pin "1") (pintype "passive"))
      (node (ref "U7") (pin "B55") (pinfunction "UART_RXD/MDC_B55") (pintype "input"))
    )
    (net (code "70") (name "Net-(U7A-UART_TXD{slash}MDIO)") (class "Default")
      (node (ref "TP14") (pin "1") (pintype "passive"))
      (node (ref "U7") (pin "A62") (pinfunction "UART_TXD/MDIO_A62") (pintype "input"))
    )
    (net (code "71") (name "Net-(U7C-AVDD25)") (class "Default")
      (node (ref "C128") (pin "1") (pinfunction "1_1") (pintype "passive"))
      (node (ref "R76") (pin "2") (pinfunction "2_2") (pintype "passive"))
      (node (ref "U7") (pin "A11") (pinfunction "AVDD25_A11") (pintype "input"))
      (node (ref "U7") (pin "A9") (pinfunction "VDD25_REG_A9") (pintype "input"))
    )
    (net (code "72") (name "Net-(U7C-AVDDVCO_I)") (class "Default")
      (node (ref "C117") (pin "2") (pinfunction "2_2") (pintype "passive"))
      (node (ref "U7") (pin "A12") (pinfunction "AVDDVCO_O_A12") (pintype "input"))
      (node (ref "U7") (pin "A34") (pinfunction "AVDDVCO_I_A34") (pintype "input"))
    )
    (net (code "73") (name "Net-(U7C-LX)") (class "Default")
      (node (ref "L5") (pin "1") (pinfunction "1_1") (pintype "passive"))
      (node (ref "U7") (pin "B75") (pinfunction "LX_B75") (pintype "input"))
    )
    (net (code "74") (name "Net-(U7C-VDD15_REG_0)") (class "Default")
      (node (ref "C115") (pin "2") (pinfunction "2_2") (pintype "passive"))
      (node (ref "U7") (pin "B59") (pinfunction "VDD15_REG_0_B59") (pintype "input"))
    )
    (net (code "75") (name "Net-(U7C-VDD15_REG_1)") (class "Default")
      (node (ref "C116") (pin "2") (pinfunction "2_2") (pintype "passive"))
      (node (ref "U7") (pin "A56") (pinfunction "VDD15_REG_1_A56") (pintype "input"))
    )
    (net (code "76") (name "unconnected-(U7A-CH3_TRXN0-PadA31)") (class "Default")
      (node (ref "U7") (pin "A31") (pinfunction "CH3_TRXN0_A31") (pintype "input+no_connect"))
    )
    (net (code "77") (name "unconnected-(U7A-CH3_TRXN1-PadB28)") (class "Default")
      (node (ref "U7") (pin "B28") (pinfunction "CH3_TRXN1_B28") (pintype "input+no_connect"))
    )
    (net (code "78") (name "unconnected-(U7A-CH3_TRXN2-PadA37)") (class "Default")
      (node (ref "U7") (pin "A37") (pinfunction "CH3_TRXN2_A37") (pintype "input+no_connect"))
    )
    (net (code "79") (name "unconnected-(U7A-CH3_TRXN3-PadB34)") (class "Default")
      (node (ref "U7") (pin "B34") (pinfunction "CH3_TRXN3_B34") (pintype "input+no_connect"))
    )
    (net (code "80") (name "unconnected-(U7A-CH3_TRXP0-PadB26)") (class "Default")
      (node (ref "U7") (pin "B26") (pinfunction "CH3_TRXP0_B26") (pintype "input+no_connect"))
    )
    (net (code "81") (name "unconnected-(U7A-CH3_TRXP1-PadA32)") (class "Default")
      (node (ref "U7") (pin "A32") (pinfunction "CH3_TRXP1_A32") (pintype "input+no_connect"))
    )
    (net (code "82") (name "unconnected-(U7A-CH3_TRXP2-PadB32)") (class "Default")
      (node (ref "U7") (pin "B32") (pinfunction "CH3_TRXP2_B32") (pintype "input+no_connect"))
    )
    (net (code "83") (name "unconnected-(U7A-CH3_TRXP3-PadA38)") (class "Default")
      (node (ref "U7") (pin "A38") (pinfunction "CH3_TRXP3_A38") (pintype "input+no_connect"))
    )
    (net (code "84") (name "unconnected-(U7A-CH4_TRXN0-PadA40)") (class "Default")
      (node (ref "U7") (pin "A40") (pinfunction "CH4_TRXN0_A40") (pintype "input+no_connect"))
    )
    (net (code "85") (name "unconnected-(U7A-CH4_TRXN1-PadB37)") (class "Default")
      (node (ref "U7") (pin "B37") (pinfunction "CH4_TRXN1_B37") (pintype "input+no_connect"))
    )
    (net (code "86") (name "unconnected-(U7A-CH4_TRXN2-PadB39)") (class "Default")
      (node (ref "U7") (pin "B39") (pinfunction "CH4_TRXN2_B39") (pintype "input+no_connect"))
    )
    (net (code "87") (name "unconnected-(U7A-CH4_TRXN3-PadA48)") (class "Default")
      (node (ref "U7") (pin "A48") (pinfunction "CH4_TRXN3_A48") (pintype "input+no_connect"))
    )
    (net (code "88") (name "unconnected-(U7A-CH4_TRXP0-PadB35)") (class "Default")
      (node (ref "U7") (pin "B35") (pinfunction "CH4_TRXP0_B35") (pintype "input+no_connect"))
    )
    (net (code "89") (name "unconnected-(U7A-CH4_TRXP1-PadA41)") (class "Default")
      (node (ref "U7") (pin "A41") (pinfunction "CH4_TRXP1_A41") (pintype "input+no_connect"))
    )
    (net (code "90") (name "unconnected-(U7A-CH4_TRXP2-PadB38)") (class "Default")
      (node (ref "U7") (pin "B38") (pinfunction "CH4_TRXP2_B38") (pintype "input+no_connect"))
    )
    (net (code "91") (name "unconnected-(U7A-CH4_TRXP3-PadB40)") (class "Default")
      (node (ref "U7") (pin "B40") (pinfunction "CH4_TRXP3_B40") (pintype "input+no_connect"))
    )
    (net (code "92") (name "unconnected-(U7A-GTXCLK_0{slash}TXCLK_0-PadA73)") (class "Default")
      (node (ref "U7") (pin "A73") (pinfunction "GTXCLK_0/TXCLK_0_A73") (pintype "input+no_connect"))
    )
    (net (code "93") (name "unconnected-(U7A-GTXCLK_1{slash}TXCLK_1-PadB51)") (class "Default")
      (node (ref "U7") (pin "B51") (pinfunction "GTXCLK_1/TXCLK_1_B51") (pintype "input+no_connect"))
    )
    (net (code "94") (name "unconnected-(U7A-RXCLK_0-PadA65)") (class "Default")
      (node (ref "U7") (pin "A65") (pinfunction "RXCLK_0_A65") (pintype "input+no_connect"))
    )
    (net (code "95") (name "unconnected-(U7A-RXCLK_1-PadB47)") (class "Default")
      (node (ref "U7") (pin "B47") (pinfunction "RXCLK_1_B47") (pintype "input+no_connect"))
    )
    (net (code "96") (name "unconnected-(U7A-RXD0_0-PadA68)") (class "Default")
      (node (ref "U7") (pin "A68") (pinfunction "RXD0_0_A68") (pintype "input+no_connect"))
    )
    (net (code "97") (name "unconnected-(U7A-RXD0_1-PadA55)") (class "Default")
      (node (ref "U7") (pin "A55") (pinfunction "RXD0_1_A55") (pintype "input+no_connect"))
    )
    (net (code "98") (name "unconnected-(U7A-RXD1_1-PadB48)") (class "Default")
      (node (ref "U7") (pin "B48") (pinfunction "RXD1_1_B48") (pintype "input+no_connect"))
    )
    (net (code "99") (name "unconnected-(U7A-RXD2_0-PadA70)") (class "Default")
      (node (ref "U7") (pin "A70") (pinfunction "RXD2_0_A70") (pintype "input+no_connect"))
    )
    (net (code "100") (name "unconnected-(U7A-RXD2_1-PadB49)") (class "Default")
      (node (ref "U7") (pin "B49") (pinfunction "RXD2_1_B49") (pintype "input+no_connect"))
    )
    (net (code "101") (name "unconnected-(U7A-RXD3_0-PadB60)") (class "Default")
      (node (ref "U7") (pin "B60") (pinfunction "RXD3_0_B60") (pintype "input+no_connect"))
    )
    (net (code "102") (name "unconnected-(U7A-RXD3_1-PadA57)") (class "Default")
      (node (ref "U7") (pin "A57") (pinfunction "RXD3_1_A57") (pintype "input+no_connect"))
    )
    (net (code "103") (name "unconnected-(U7A-RXDV_0{slash}RXCTR_0-PadA64)") (class "Default")
      (node (ref "U7") (pin "A64") (pinfunction "RXDV_0/RXCTR_0_A64") (pintype "input+no_connect"))
    )
    (net (code "104") (name "unconnected-(U7A-RXDV_1{slash}RXCTR_1-PadA54)") (class "Default")
      (node (ref "U7") (pin "A54") (pinfunction "RXDV_1/RXCTR_1_A54") (pintype "input+no_connect"))
    )
    (net (code "105") (name "unconnected-(U7A-SIN-PadB67)") (class "Default")
      (node (ref "U7") (pin "B67") (pinfunction "SIN_B67") (pintype "input+no_connect"))
    )
    (net (code "106") (name "unconnected-(U7A-SIP-PadA78)") (class "Default")
      (node (ref "U7") (pin "A78") (pinfunction "SIP_A78") (pintype "input+no_connect"))
    )
    (net (code "107") (name "unconnected-(U7A-SON-PadA76)") (class "Default")
      (node (ref "U7") (pin "A76") (pinfunction "SON_A76") (pintype "input+no_connect"))
    )
    (net (code "108") (name "unconnected-(U7A-SOP-PadB66)") (class "Default")
      (node (ref "U7") (pin "B66") (pinfunction "SOP_B66") (pintype "input+no_connect"))
    )
    (net (code "109") (name "unconnected-(U7A-TXD0_0-PadB63)") (class "Default")
      (node (ref "U7") (pin "B63") (pinfunction "TXD0_0_B63") (pintype "input+no_connect"))
    )
    (net (code "110") (name "unconnected-(U7A-TXD0_1-PadA59)") (class "Default")
      (node (ref "U7") (pin "A59") (pinfunction "TXD0_1_A59") (pintype "input+no_connect"))
    )
    (net (code "111") (name "unconnected-(U7A-TXD1_0-PadA74)") (class "Default")
      (node (ref "U7") (pin "A74") (pinfunction "TXD1_0_A74") (pintype "input+no_connect"))
    )
    (net (code "112") (name "unconnected-(U7A-TXD1_1-PadB52)") (class "Default")
      (node (ref "U7") (pin "B52") (pinfunction "TXD1_1_B52") (pintype "input+no_connect"))
    )
    (net (code "113") (name "unconnected-(U7A-TXD2_0-PadB64)") (class "Default")
      (node (ref "U7") (pin "B64") (pinfunction "TXD2_0_B64") (pintype "input+no_connect"))
    )
    (net (code "114") (name "unconnected-(U7A-TXD2_1-PadA60)") (class "Default")
      (node (ref "U7") (pin "A60") (pinfunction "TXD2_1_A60") (pintype "input+no_connect"))
    )
    (net (code "115") (name "unconnected-(U7A-TXD3_0-PadA75)") (class "Default")
      (node (ref "U7") (pin "A75") (pinfunction "TXD3_0_A75") (pintype "input+no_connect"))
    )
    (net (code "116") (name "unconnected-(U7A-TXD3_1-PadB53)") (class "Default")
      (node (ref "U7") (pin "B53") (pinfunction "TXD3_1_B53") (pintype "input+no_connect"))
    )
    (net (code "117") (name "unconnected-(U7A-TXEN{slash}TXCTR_0-PadA72)") (class "Default")
      (node (ref "U7") (pin "A72") (pinfunction "TXEN/TXCTR_0_A72") (pintype "input+no_connect"))
    )
    (net (code "118") (name "unconnected-(U7A-TXEN{slash}TXCTR_1-PadA58)") (class "Default")
      (node (ref "U7") (pin "A58") (pinfunction "TXEN/TXCTR_1_A58") (pintype "input+no_connect"))
    )
    (net (code "119") (name "unconnected-(U7B-LED_LINK10n_3-PadA84)") (class "Default")
      (node (ref "U7") (pin "A84") (pinfunction "LED_LINK10n_3_A84") (pintype "input+no_connect"))
    )
    (net (code "120") (name "unconnected-(U7B-LED_LINK10n_4-PadA49)") (class "Default")
      (node (ref "U7") (pin "A49") (pinfunction "LED_LINK10n_4_A49") (pintype "input+no_connect"))
    )
    (net (code "121") (name "unconnected-(U7B-LED_LINK100n_3-PadB74)") (class "Default")
      (node (ref "U7") (pin "B74") (pinfunction "LED_LINK100n_3_B74") (pintype "input+no_connect"))
    )
    (net (code "122") (name "unconnected-(U7B-LED_LINK100n_4-PadB42)") (class "Default")
      (node (ref "U7") (pin "B42") (pinfunction "LED_LINK100n_4_B42") (pintype "input+no_connect"))
    )
    (net (code "123") (name "unconnected-(U7B-LED_LINK1000n_3-PadA85)") (class "Default")
      (node (ref "U7") (pin "A85") (pinfunction "LED_LINK1000n_3_A85") (pintype "input+no_connect"))
    )
    (net (code "124") (name "unconnected-(U7B-LED_LINK1000n_4-PadA50)") (class "Default")
      (node (ref "U7") (pin "A50") (pinfunction "LED_LINK1000n_4_A50") (pintype "input+no_connect"))
    )
  )
)
